# robot.net
KiCad netlist of a schematic drawn in EAGLE
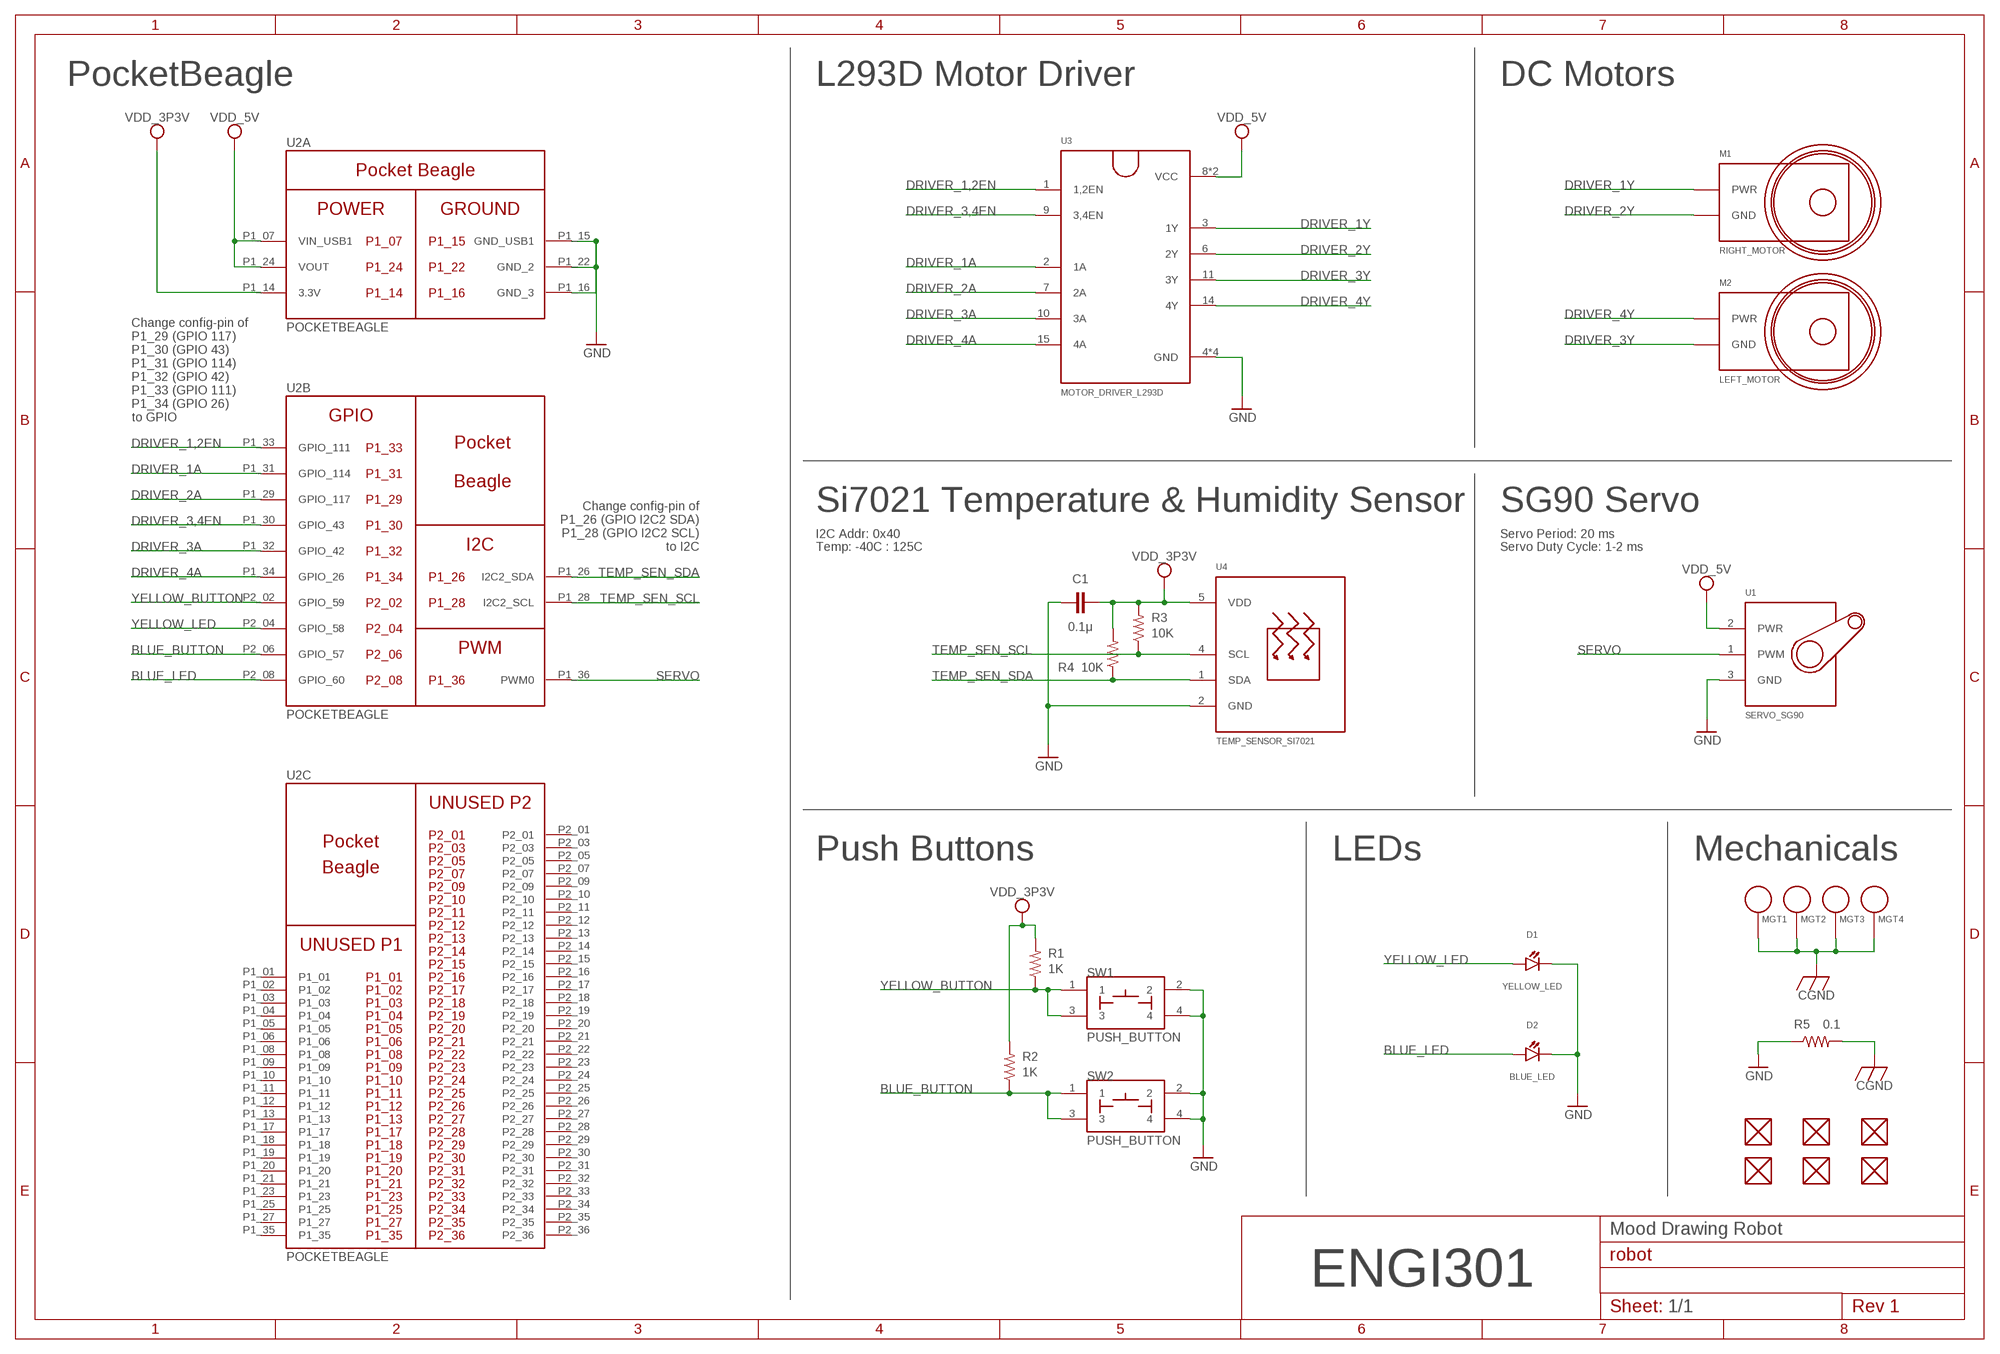
[diagram p0: schematic, sheet 1]

(export (version "E")
  (design (tool "Eeschema 10.0.6"))
  (components
    (comp (ref "C1")
      (value "0.1μ")
      (footprint "eagle-import:C0603")
      (libsource (lib "eagle-import") (part "C_C0603"))
    )
    (comp (ref "D1")
      (value "YELLOW_LED")
      (footprint "eagle-import:LED_EIA_STD")
      (libsource (lib "eagle-import") (part "LED"))
    )
    (comp (ref "D2")
      (value "BLUE_LED")
      (footprint "eagle-import:LED_EIA_STD")
      (libsource (lib "eagle-import") (part "LED"))
    )
    (comp (ref "FUD1")
      (value "FIDUCIAL")
      (footprint "eagle-import:FIDUCIAL_40MIL")
      (libsource (lib "eagle-import") (part "FIDUCIAL"))
    )
    (comp (ref "FUD2")
      (value "FIDUCIAL")
      (footprint "eagle-import:FIDUCIAL_40MIL")
      (libsource (lib "eagle-import") (part "FIDUCIAL"))
    )
    (comp (ref "FUD3")
      (value "FIDUCIAL")
      (footprint "eagle-import:FIDUCIAL_40MIL")
      (libsource (lib "eagle-import") (part "FIDUCIAL"))
    )
    (comp (ref "FUD4")
      (value "FIDUCIAL")
      (footprint "eagle-import:FIDUCIAL_40MIL")
      (libsource (lib "eagle-import") (part "FIDUCIAL"))
    )
    (comp (ref "FUD5")
      (value "FIDUCIAL")
      (footprint "eagle-import:FIDUCIAL_40MIL")
      (libsource (lib "eagle-import") (part "FIDUCIAL"))
    )
    (comp (ref "FUD6")
      (value "FIDUCIAL")
      (footprint "eagle-import:FIDUCIAL_40MIL")
      (libsource (lib "eagle-import") (part "FIDUCIAL"))
    )
    (comp (ref "M1")
      (value "RIGHT_MOTOR")
      (footprint "eagle-import:DC_MOTOR")
      (libsource (lib "eagle-import") (part "DC_MOTOR"))
    )
    (comp (ref "M2")
      (value "LEFT_MOTOR")
      (footprint "eagle-import:DC_MOTOR")
      (libsource (lib "eagle-import") (part "DC_MOTOR"))
    )
    (comp (ref "MGT1")
      (value "MOUNTING_HOLE")
      (footprint "eagle-import:MOUNTING_HOLE")
      (libsource (lib "eagle-import") (part "MOUNTING_HOLE"))
    )
    (comp (ref "MGT2")
      (value "MOUNTING_HOLE")
      (footprint "eagle-import:MOUNTING_HOLE")
      (libsource (lib "eagle-import") (part "MOUNTING_HOLE"))
    )
    (comp (ref "MGT3")
      (value "MOUNTING_HOLE")
      (footprint "eagle-import:MOUNTING_HOLE")
      (libsource (lib "eagle-import") (part "MOUNTING_HOLE"))
    )
    (comp (ref "MGT4")
      (value "MOUNTING_HOLE")
      (footprint "eagle-import:MOUNTING_HOLE")
      (libsource (lib "eagle-import") (part "MOUNTING_HOLE"))
    )
    (comp (ref "R1")
      (value "1K")
      (footprint "eagle-import:R0603")
      (libsource (lib "eagle-import") (part "R_R0603"))
    )
    (comp (ref "R2")
      (value "1K")
      (footprint "eagle-import:R0603")
      (libsource (lib "eagle-import") (part "R_R0603"))
    )
    (comp (ref "R3")
      (value "10K")
      (footprint "eagle-import:R0603")
      (libsource (lib "eagle-import") (part "R_R0603"))
    )
    (comp (ref "R4")
      (value "10K")
      (footprint "eagle-import:R0603")
      (libsource (lib "eagle-import") (part "R_R0603"))
    )
    (comp (ref "R5")
      (value "0.1")
      (footprint "eagle-import:R0805")
      (libsource (lib "eagle-import") (part "R_R0805"))
    )
    (comp (ref "SW1")
      (value "PUSH_BUTTON")
      (footprint "eagle-import:PUSH_BUTTON_12.5MM")
      (libsource (lib "eagle-import") (part "PUSH_BUTTON"))
    )
    (comp (ref "SW2")
      (value "PUSH_BUTTON")
      (footprint "eagle-import:PUSH_BUTTON_12.5MM")
      (libsource (lib "eagle-import") (part "PUSH_BUTTON"))
    )
    (comp (ref "U1")
      (value "SERVO_SG90")
      (footprint "eagle-import:SERVO")
      (libsource (lib "eagle-import") (part "SERVO_SG90"))
    )
    (comp (ref "U2")
      (value "POCKETBEAGLE")
      (footprint "eagle-import:POCKETBEAGLE")
      (libsource (lib "eagle-import") (part "POCKETBEAGLE"))
    )
    (comp (ref "U3")
      (value "MOTOR_DRIVER_L293D")
      (footprint "eagle-import:MOTOR_DRIVER")
      (libsource (lib "eagle-import") (part "MOTOR_DRIVER_L293D"))
    )
    (comp (ref "U4")
      (value "TEMP_SENSOR_SI7021")
      (footprint "eagle-import:TEMP_SENSOR")
      (libsource (lib "eagle-import") (part "TEMP_SENSOR_SI7021"))
    )
  )
  (nets
    (net (code "1") (name "/BLUE_BUTTON") (class "Default")
      (node (ref "R2") (pin "1") (pinfunction "1_1") (pintype "passive"))
      (node (ref "SW2") (pin "1") (pinfunction "1_1") (pintype "bidirectional"))
      (node (ref "SW2") (pin "3") (pinfunction "3_3") (pintype "bidirectional"))
      (node (ref "U2") (pin "P2_06") (pinfunction "GPIO_57_P2_06") (pintype "bidirectional"))
    )
    (net (code "2") (name "/BLUE_LED") (class "Default")
      (node (ref "D2") (pin "ANODE") (pinfunction "ANODE_ANODE") (pintype "bidirectional"))
      (node (ref "U2") (pin "P2_08") (pinfunction "GPIO_60_P2_08") (pintype "bidirectional"))
    )
    (net (code "3") (name "/DRIVER_1,2EN") (class "Default")
      (node (ref "U2") (pin "P1_33") (pinfunction "GPIO_111_P1_33") (pintype "bidirectional"))
      (node (ref "U3") (pin "1") (pinfunction "1,2EN_1") (pintype "bidirectional"))
    )
    (net (code "4") (name "/DRIVER_1A") (class "Default")
      (node (ref "U2") (pin "P1_31") (pinfunction "GPIO_114_P1_31") (pintype "bidirectional"))
      (node (ref "U3") (pin "2") (pinfunction "1A_2") (pintype "bidirectional"))
    )
    (net (code "5") (name "/DRIVER_1Y") (class "Default")
      (node (ref "M1") (pin "PWR") (pinfunction "PWR_PWR") (pintype "bidirectional"))
      (node (ref "U3") (pin "3") (pinfunction "1Y_3") (pintype "bidirectional"))
    )
    (net (code "6") (name "/DRIVER_2A") (class "Default")
      (node (ref "U2") (pin "P1_29") (pinfunction "GPIO_117_P1_29") (pintype "bidirectional"))
      (node (ref "U3") (pin "7") (pinfunction "2A_7") (pintype "bidirectional"))
    )
    (net (code "7") (name "/DRIVER_2Y") (class "Default")
      (node (ref "M1") (pin "GND") (pinfunction "GND_GND") (pintype "bidirectional"))
      (node (ref "U3") (pin "6") (pinfunction "2Y_6") (pintype "bidirectional"))
    )
    (net (code "8") (name "/DRIVER_3,4EN") (class "Default")
      (node (ref "U2") (pin "P1_30") (pinfunction "GPIO_43_P1_30") (pintype "bidirectional"))
      (node (ref "U3") (pin "9") (pinfunction "3,4EN_9") (pintype "bidirectional"))
    )
    (net (code "9") (name "/DRIVER_3A") (class "Default")
      (node (ref "U2") (pin "P1_32") (pinfunction "GPIO_42_P1_32") (pintype "bidirectional"))
      (node (ref "U3") (pin "10") (pinfunction "3A_10") (pintype "bidirectional"))
    )
    (net (code "10") (name "/DRIVER_3Y") (class "Default")
      (node (ref "M2") (pin "GND") (pinfunction "GND_GND") (pintype "bidirectional"))
      (node (ref "U3") (pin "11") (pinfunction "3Y_11") (pintype "bidirectional"))
    )
    (net (code "11") (name "/DRIVER_4A") (class "Default")
      (node (ref "U2") (pin "P1_34") (pinfunction "GPIO_26_P1_34") (pintype "bidirectional"))
      (node (ref "U3") (pin "15") (pinfunction "4A_15") (pintype "bidirectional"))
    )
    (net (code "12") (name "/DRIVER_4Y") (class "Default")
      (node (ref "M2") (pin "PWR") (pinfunction "PWR_PWR") (pintype "bidirectional"))
      (node (ref "U3") (pin "14") (pinfunction "4Y_14") (pintype "bidirectional"))
    )
    (net (code "13") (name "/SERVO") (class "Default")
      (node (ref "U1") (pin "1") (pinfunction "PWM_1") (pintype "bidirectional"))
      (node (ref "U2") (pin "P1_36") (pinfunction "PWM0_P1_36") (pintype "bidirectional"))
    )
    (net (code "14") (name "/TEMP_SEN_SCL") (class "Default")
      (node (ref "R3") (pin "1") (pinfunction "1_1") (pintype "passive"))
      (node (ref "U2") (pin "P1_28") (pinfunction "I2C2_SCL_P1_28") (pintype "bidirectional"))
      (node (ref "U4") (pin "4") (pinfunction "SCL_4") (pintype "bidirectional"))
    )
    (net (code "15") (name "/TEMP_SEN_SDA") (class "Default")
      (node (ref "R4") (pin "1") (pinfunction "1_1") (pintype "passive"))
      (node (ref "U2") (pin "P1_26") (pinfunction "I2C2_SDA_P1_26") (pintype "bidirectional"))
      (node (ref "U4") (pin "1") (pinfunction "SDA_1") (pintype "bidirectional"))
    )
    (net (code "16") (name "/YELLOW_BUTTON") (class "Default")
      (node (ref "R1") (pin "1") (pinfunction "1_1") (pintype "passive"))
      (node (ref "SW1") (pin "1") (pinfunction "1_1") (pintype "bidirectional"))
      (node (ref "SW1") (pin "3") (pinfunction "3_3") (pintype "bidirectional"))
      (node (ref "U2") (pin "P2_02") (pinfunction "GPIO_59_P2_02") (pintype "bidirectional"))
    )
    (net (code "17") (name "/YELLOW_LED") (class "Default")
      (node (ref "D1") (pin "ANODE") (pinfunction "ANODE_ANODE") (pintype "bidirectional"))
      (node (ref "U2") (pin "P2_04") (pinfunction "GPIO_58_P2_04") (pintype "bidirectional"))
    )
    (net (code "18") (name "CGND") (class "Default")
      (node (ref "MGT1") (pin "P$1") (pinfunction "P$1_P$1") (pintype "bidirectional"))
      (node (ref "MGT2") (pin "P$1") (pinfunction "P$1_P$1") (pintype "bidirectional"))
      (node (ref "MGT3") (pin "P$1") (pinfunction "P$1_P$1") (pintype "bidirectional"))
      (node (ref "MGT4") (pin "P$1") (pinfunction "P$1_P$1") (pintype "bidirectional"))
      (node (ref "R5") (pin "2") (pinfunction "2_2") (pintype "passive"))
    )
    (net (code "19") (name "GND") (class "Default")
      (node (ref "C1") (pin "1") (pinfunction "1_1") (pintype "passive"))
      (node (ref "D1") (pin "CATHODE") (pinfunction "CATHODE_CATHODE") (pintype "bidirectional"))
      (node (ref "D2") (pin "CATHODE") (pinfunction "CATHODE_CATHODE") (pintype "bidirectional"))
      (node (ref "R5") (pin "1") (pinfunction "1_1") (pintype "passive"))
      (node (ref "SW1") (pin "2") (pinfunction "2_2") (pintype "bidirectional"))
      (node (ref "SW1") (pin "4") (pinfunction "4_4") (pintype "bidirectional"))
      (node (ref "SW2") (pin "2") (pinfunction "2_2") (pintype "bidirectional"))
      (node (ref "SW2") (pin "4") (pinfunction "4_4") (pintype "bidirectional"))
      (node (ref "U1") (pin "3") (pinfunction "GND_3") (pintype "bidirectional"))
      (node (ref "U2") (pin "P1_15") (pinfunction "GND_USB1_P1_15") (pintype "bidirectional"))
      (node (ref "U2") (pin "P1_16") (pinfunction "GND_3_P1_16") (pintype "bidirectional"))
      (node (ref "U2") (pin "P1_22") (pinfunction "GND_2_P1_22") (pintype "bidirectional"))
      (node (ref "U3") (pin "12") (pinfunction "GND_12") (pintype "bidirectional"))
      (node (ref "U3") (pin "13") (pinfunction "GND_13") (pintype "bidirectional"))
      (node (ref "U3") (pin "4") (pinfunction "GND_4") (pintype "bidirectional"))
      (node (ref "U3") (pin "5") (pinfunction "GND_5") (pintype "bidirectional"))
      (node (ref "U4") (pin "2") (pinfunction "GND_2") (pintype "bidirectional"))
    )
    (net (code "20") (name "VDD_3P3V") (class "Default")
      (node (ref "C1") (pin "2") (pinfunction "2_2") (pintype "passive"))
      (node (ref "R1") (pin "2") (pinfunction "2_2") (pintype "passive"))
      (node (ref "R2") (pin "2") (pinfunction "2_2") (pintype "passive"))
      (node (ref "R3") (pin "2") (pinfunction "2_2") (pintype "passive"))
      (node (ref "R4") (pin "2") (pinfunction "2_2") (pintype "passive"))
      (node (ref "U2") (pin "P1_14") (pinfunction "3.3V_P1_14") (pintype "power_in"))
      (node (ref "U4") (pin "5") (pinfunction "VDD_5") (pintype "power_in"))
    )
    (net (code "21") (name "VDD_5V") (class "Default")
      (node (ref "U1") (pin "2") (pinfunction "PWR_2") (pintype "power_in"))
      (node (ref "U2") (pin "P1_07") (pinfunction "VIN_USB1_P1_07") (pintype "power_in"))
      (node (ref "U2") (pin "P1_24") (pinfunction "VOUT_P1_24") (pintype "power_in"))
      (node (ref "U3") (pin "16") (pinfunction "VCC_16") (pintype "power_in"))
      (node (ref "U3") (pin "8") (pinfunction "VCC_8") (pintype "power_in"))
    )
    (net (code "22") (name "unconnected-(FUD1-PadP$1)") (class "Default")
      (node (ref "FUD1") (pin "P$1") (pinfunction "P$1_P$1") (pintype "no_connect"))
    )
    (net (code "23") (name "unconnected-(FUD2-PadP$1)") (class "Default")
      (node (ref "FUD2") (pin "P$1") (pinfunction "P$1_P$1") (pintype "no_connect"))
    )
    (net (code "24") (name "unconnected-(FUD3-PadP$1)") (class "Default")
      (node (ref "FUD3") (pin "P$1") (pinfunction "P$1_P$1") (pintype "no_connect"))
    )
    (net (code "25") (name "unconnected-(FUD4-PadP$1)") (class "Default")
      (node (ref "FUD4") (pin "P$1") (pinfunction "P$1_P$1") (pintype "no_connect"))
    )
    (net (code "26") (name "unconnected-(FUD5-PadP$1)") (class "Default")
      (node (ref "FUD5") (pin "P$1") (pinfunction "P$1_P$1") (pintype "no_connect"))
    )
    (net (code "27") (name "unconnected-(FUD6-PadP$1)") (class "Default")
      (node (ref "FUD6") (pin "P$1") (pinfunction "P$1_P$1") (pintype "no_connect"))
    )
    (net (code "28") (name "unconnected-(U2-PadP1_01)") (class "Default")
      (node (ref "U2") (pin "P1_01") (pinfunction "P1_01_P1_01") (pintype "bidirectional"))
    )
    (net (code "29") (name "unconnected-(U2-PadP1_02)") (class "Default")
      (node (ref "U2") (pin "P1_02") (pinfunction "P1_02_P1_02") (pintype "bidirectional"))
    )
    (net (code "30") (name "unconnected-(U2-PadP1_03)") (class "Default")
      (node (ref "U2") (pin "P1_03") (pinfunction "P1_03_P1_03") (pintype "bidirectional"))
    )
    (net (code "31") (name "unconnected-(U2-PadP1_04)") (class "Default")
      (node (ref "U2") (pin "P1_04") (pinfunction "P1_04_P1_04") (pintype "bidirectional"))
    )
    (net (code "32") (name "unconnected-(U2-PadP1_05)") (class "Default")
      (node (ref "U2") (pin "P1_05") (pinfunction "P1_05_P1_05") (pintype "bidirectional"))
    )
    (net (code "33") (name "unconnected-(U2-PadP1_06)") (class "Default")
      (node (ref "U2") (pin "P1_06") (pinfunction "P1_06_P1_06") (pintype "bidirectional"))
    )
    (net (code "34") (name "unconnected-(U2-PadP1_08)") (class "Default")
      (node (ref "U2") (pin "P1_08") (pinfunction "P1_08_P1_08") (pintype "bidirectional"))
    )
    (net (code "35") (name "unconnected-(U2-PadP1_09)") (class "Default")
      (node (ref "U2") (pin "P1_09") (pinfunction "P1_09_P1_09") (pintype "bidirectional"))
    )
    (net (code "36") (name "unconnected-(U2-PadP1_10)") (class "Default")
      (node (ref "U2") (pin "P1_10") (pinfunction "P1_10_P1_10") (pintype "bidirectional"))
    )
    (net (code "37") (name "unconnected-(U2-PadP1_11)") (class "Default")
      (node (ref "U2") (pin "P1_11") (pinfunction "P1_11_P1_11") (pintype "bidirectional"))
    )
    (net (code "38") (name "unconnected-(U2-PadP1_12)") (class "Default")
      (node (ref "U2") (pin "P1_12") (pinfunction "P1_12_P1_12") (pintype "bidirectional"))
    )
    (net (code "39") (name "unconnected-(U2-PadP1_13)") (class "Default")
      (node (ref "U2") (pin "P1_13") (pinfunction "P1_13_P1_13") (pintype "bidirectional"))
    )
    (net (code "40") (name "unconnected-(U2-PadP1_17)") (class "Default")
      (node (ref "U2") (pin "P1_17") (pinfunction "P1_17_P1_17") (pintype "bidirectional"))
    )
    (net (code "41") (name "unconnected-(U2-PadP1_18)") (class "Default")
      (node (ref "U2") (pin "P1_18") (pinfunction "P1_18_P1_18") (pintype "bidirectional"))
    )
    (net (code "42") (name "unconnected-(U2-PadP1_19)") (class "Default")
      (node (ref "U2") (pin "P1_19") (pinfunction "P1_19_P1_19") (pintype "bidirectional"))
    )
    (net (code "43") (name "unconnected-(U2-PadP1_20)") (class "Default")
      (node (ref "U2") (pin "P1_20") (pinfunction "P1_20_P1_20") (pintype "bidirectional"))
    )
    (net (code "44") (name "unconnected-(U2-PadP1_21)") (class "Default")
      (node (ref "U2") (pin "P1_21") (pinfunction "P1_21_P1_21") (pintype "bidirectional"))
    )
    (net (code "45") (name "unconnected-(U2-PadP1_23)") (class "Default")
      (node (ref "U2") (pin "P1_23") (pinfunction "P1_23_P1_23") (pintype "bidirectional"))
    )
    (net (code "46") (name "unconnected-(U2-PadP1_25)") (class "Default")
      (node (ref "U2") (pin "P1_25") (pinfunction "P1_25_P1_25") (pintype "bidirectional"))
    )
    (net (code "47") (name "unconnected-(U2-PadP1_27)") (class "Default")
      (node (ref "U2") (pin "P1_27") (pinfunction "P1_27_P1_27") (pintype "bidirectional"))
    )
    (net (code "48") (name "unconnected-(U2-PadP1_35)") (class "Default")
      (node (ref "U2") (pin "P1_35") (pinfunction "P1_35_P1_35") (pintype "bidirectional"))
    )
    (net (code "49") (name "unconnected-(U2-PadP2_01)") (class "Default")
      (node (ref "U2") (pin "P2_01") (pinfunction "P2_01_P2_01") (pintype "bidirectional"))
    )
    (net (code "50") (name "unconnected-(U2-PadP2_03)") (class "Default")
      (node (ref "U2") (pin "P2_03") (pinfunction "P2_03_P2_03") (pintype "bidirectional"))
    )
    (net (code "51") (name "unconnected-(U2-PadP2_05)") (class "Default")
      (node (ref "U2") (pin "P2_05") (pinfunction "P2_05_P2_05") (pintype "bidirectional"))
    )
    (net (code "52") (name "unconnected-(U2-PadP2_07)") (class "Default")
      (node (ref "U2") (pin "P2_07") (pinfunction "P2_07_P2_07") (pintype "bidirectional"))
    )
    (net (code "53") (name "unconnected-(U2-PadP2_09)") (class "Default")
      (node (ref "U2") (pin "P2_09") (pinfunction "P2_09_P2_09") (pintype "bidirectional"))
    )
    (net (code "54") (name "unconnected-(U2-PadP2_10)") (class "Default")
      (node (ref "U2") (pin "P2_10") (pinfunction "P2_10_P2_10") (pintype "bidirectional"))
    )
    (net (code "55") (name "unconnected-(U2-PadP2_11)") (class "Default")
      (node (ref "U2") (pin "P2_11") (pinfunction "P2_11_P2_11") (pintype "bidirectional"))
    )
    (net (code "56") (name "unconnected-(U2-PadP2_12)") (class "Default")
      (node (ref "U2") (pin "P2_12") (pinfunction "P2_12_P2_12") (pintype "bidirectional"))
    )
    (net (code "57") (name "unconnected-(U2-PadP2_13)") (class "Default")
      (node (ref "U2") (pin "P2_13") (pinfunction "P2_13_P2_13") (pintype "bidirectional"))
    )
    (net (code "58") (name "unconnected-(U2-PadP2_14)") (class "Default")
      (node (ref "U2") (pin "P2_14") (pinfunction "P2_14_P2_14") (pintype "bidirectional"))
    )
    (net (code "59") (name "unconnected-(U2-PadP2_15)") (class "Default")
      (node (ref "U2") (pin "P2_15") (pinfunction "P2_15_P2_15") (pintype "bidirectional"))
    )
    (net (code "60") (name "unconnected-(U2-PadP2_16)") (class "Default")
      (node (ref "U2") (pin "P2_16") (pinfunction "P2_16_P2_16") (pintype "bidirectional"))
    )
    (net (code "61") (name "unconnected-(U2-PadP2_17)") (class "Default")
      (node (ref "U2") (pin "P2_17") (pinfunction "P2_17_P2_17") (pintype "bidirectional"))
    )
    (net (code "62") (name "unconnected-(U2-PadP2_18)") (class "Default")
      (node (ref "U2") (pin "P2_18") (pinfunction "P2_18_P2_18") (pintype "bidirectional"))
    )
    (net (code "63") (name "unconnected-(U2-PadP2_19)") (class "Default")
      (node (ref "U2") (pin "P2_19") (pinfunction "P2_19_P2_19") (pintype "bidirectional"))
    )
    (net (code "64") (name "unconnected-(U2-PadP2_20)") (class "Default")
      (node (ref "U2") (pin "P2_20") (pinfunction "P2_20_P2_20") (pintype "bidirectional"))
    )
    (net (code "65") (name "unconnected-(U2-PadP2_21)") (class "Default")
      (node (ref "U2") (pin "P2_21") (pinfunction "P2_21_P2_21") (pintype "bidirectional"))
    )
    (net (code "66") (name "unconnected-(U2-PadP2_22)") (class "Default")
      (node (ref "U2") (pin "P2_22") (pinfunction "P2_22_P2_22") (pintype "bidirectional"))
    )
    (net (code "67") (name "unconnected-(U2-PadP2_23)") (class "Default")
      (node (ref "U2") (pin "P2_23") (pinfunction "P2_23_P2_23") (pintype "bidirectional"))
    )
    (net (code "68") (name "unconnected-(U2-PadP2_24)") (class "Default")
      (node (ref "U2") (pin "P2_24") (pinfunction "P2_24_P2_24") (pintype "bidirectional"))
    )
    (net (code "69") (name "unconnected-(U2-PadP2_25)") (class "Default")
      (node (ref "U2") (pin "P2_25") (pinfunction "P2_25_P2_25") (pintype "bidirectional"))
    )
    (net (code "70") (name "unconnected-(U2-PadP2_26)") (class "Default")
      (node (ref "U2") (pin "P2_26") (pinfunction "P2_26_P2_26") (pintype "bidirectional"))
    )
    (net (code "71") (name "unconnected-(U2-PadP2_27)") (class "Default")
      (node (ref "U2") (pin "P2_27") (pinfunction "P2_27_P2_27") (pintype "bidirectional"))
    )
    (net (code "72") (name "unconnected-(U2-PadP2_28)") (class "Default")
      (node (ref "U2") (pin "P2_28") (pinfunction "P2_28_P2_28") (pintype "bidirectional"))
    )
    (net (code "73") (name "unconnected-(U2-PadP2_29)") (class "Default")
      (node (ref "U2") (pin "P2_29") (pinfunction "P2_29_P2_29") (pintype "bidirectional"))
    )
    (net (code "74") (name "unconnected-(U2-PadP2_30)") (class "Default")
      (node (ref "U2") (pin "P2_30") (pinfunction "P2_30_P2_30") (pintype "bidirectional"))
    )
    (net (code "75") (name "unconnected-(U2-PadP2_31)") (class "Default")
      (node (ref "U2") (pin "P2_31") (pinfunction "P2_31_P2_31") (pintype "bidirectional"))
    )
    (net (code "76") (name "unconnected-(U2-PadP2_32)") (class "Default")
      (node (ref "U2") (pin "P2_32") (pinfunction "P2_32_P2_32") (pintype "bidirectional"))
    )
    (net (code "77") (name "unconnected-(U2-PadP2_33)") (class "Default")
      (node (ref "U2") (pin "P2_33") (pinfunction "P2_33_P2_33") (pintype "bidirectional"))
    )
    (net (code "78") (name "unconnected-(U2-PadP2_34)") (class "Default")
      (node (ref "U2") (pin "P2_34") (pinfunction "P2_34_P2_34") (pintype "bidirectional"))
    )
    (net (code "79") (name "unconnected-(U2-PadP2_35)") (class "Default")
      (node (ref "U2") (pin "P2_35") (pinfunction "P2_35_P2_35") (pintype "bidirectional"))
    )
    (net (code "80") (name "unconnected-(U2-PadP2_36)") (class "Default")
      (node (ref "U2") (pin "P2_36") (pinfunction "P2_36_P2_36") (pintype "bidirectional"))
    )
  )
)
